# Sheet6.net
KiCad netlist of a schematic drawn in Altium Designer
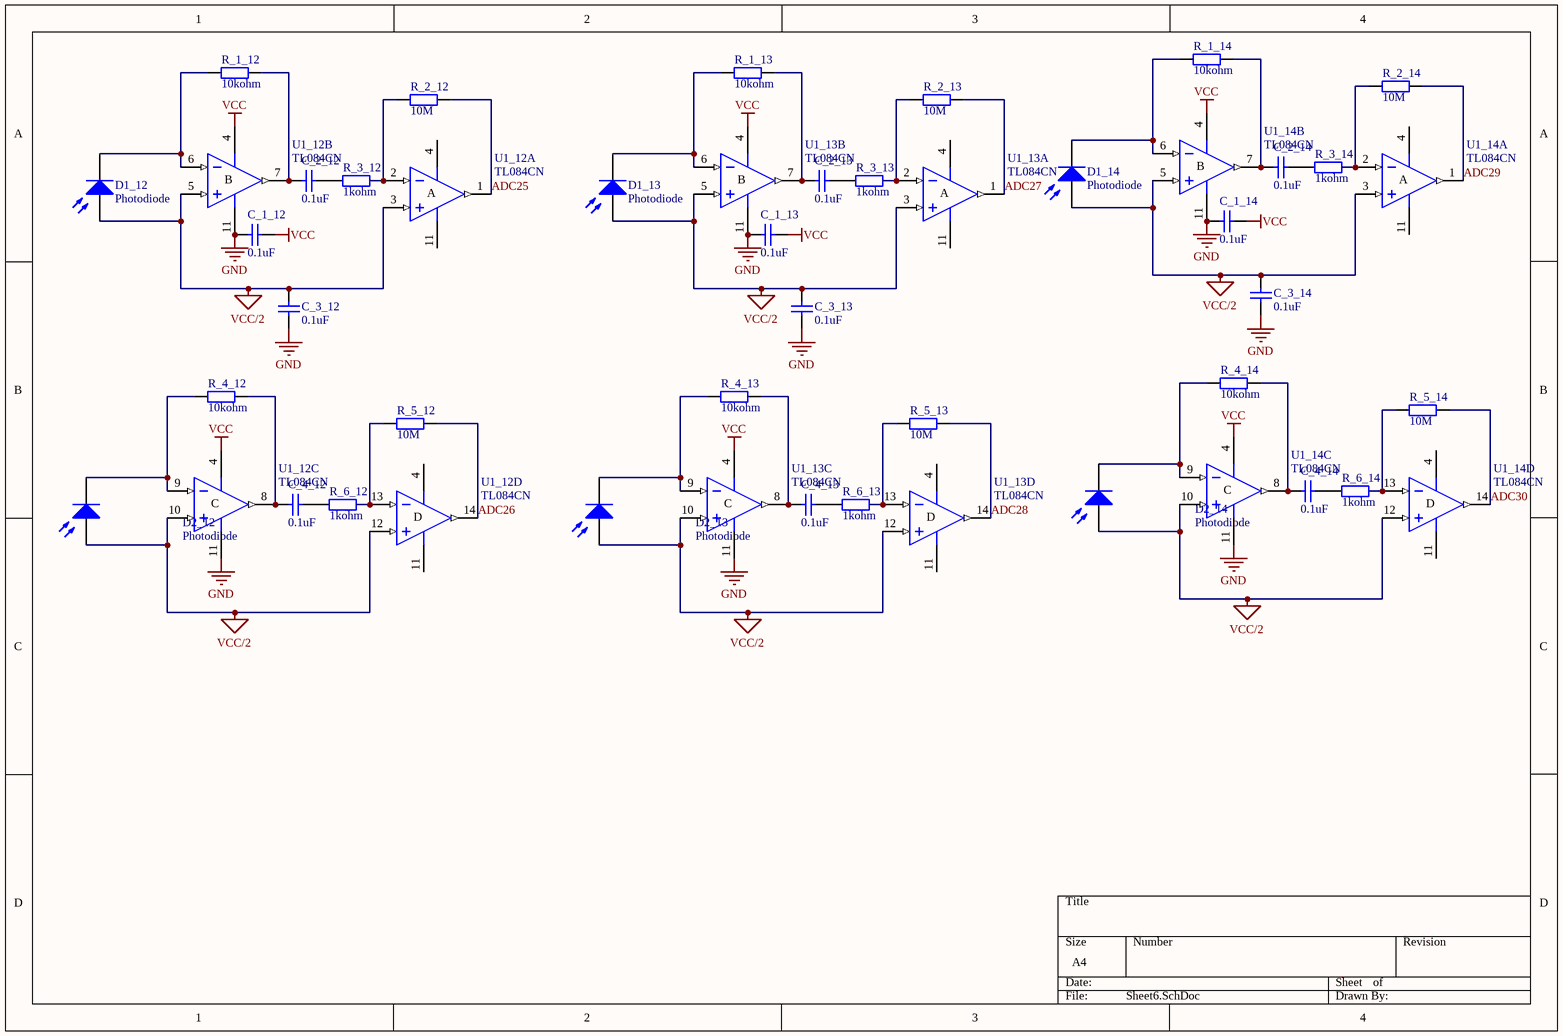
[diagram p0: Sheet6.SchDoc]

(export (version "E")
  (design (tool "Eeschema 10.0.6"))
  (components
    (comp (ref "C_1_12")
      (value "0.1uF")
      (footprint "cms805 - mini")
      (libsource (lib "lib_Robotronik") (part "Capa"))
    )
    (comp (ref "C_1_13")
      (value "0.1uF")
      (footprint "cms805 - mini")
      (libsource (lib "lib_Robotronik") (part "Capa"))
    )
    (comp (ref "C_1_14")
      (value "0.1uF")
      (footprint "cms805 - mini")
      (libsource (lib "lib_Robotronik") (part "Capa"))
    )
    (comp (ref "C_2_12")
      (value "0.1uF")
      (footprint "cms805 - mini")
      (libsource (lib "lib_Robotronik") (part "Capa"))
    )
    (comp (ref "C_2_13")
      (value "0.1uF")
      (footprint "cms805 - mini")
      (libsource (lib "lib_Robotronik") (part "Capa"))
    )
    (comp (ref "C_2_14")
      (value "0.1uF")
      (footprint "cms805 - mini")
      (libsource (lib "lib_Robotronik") (part "Capa"))
    )
    (comp (ref "C_3_12")
      (value "0.1uF")
      (footprint "cms805 - mini")
      (libsource (lib "lib_Robotronik") (part "Capa"))
    )
    (comp (ref "C_3_13")
      (value "0.1uF")
      (footprint "cms805 - mini")
      (libsource (lib "lib_Robotronik") (part "Capa"))
    )
    (comp (ref "C_3_14")
      (value "0.1uF")
      (footprint "cms805 - mini")
      (libsource (lib "lib_Robotronik") (part "Capa"))
    )
    (comp (ref "C_4_12")
      (value "0.1uF")
      (footprint "cms805 - mini")
      (libsource (lib "lib_Robotronik") (part "Capa"))
    )
    (comp (ref "C_4_13")
      (value "0.1uF")
      (footprint "cms805 - mini")
      (libsource (lib "lib_Robotronik") (part "Capa"))
    )
    (comp (ref "C_4_14")
      (value "0.1uF")
      (footprint "cms805 - mini")
      (libsource (lib "lib_Robotronik") (part "Capa"))
    )
    (comp (ref "D1_12")
      (value "Photodiode")
      (footprint "TEMD1000")
      (fields (field (name "PUBLISHER") "Altium Limited"))
      (libsource (lib "lib_Robotronik") (part "Photodiode"))
    )
    (comp (ref "D1_13")
      (value "Photodiode")
      (footprint "TEMD1000")
      (fields (field (name "PUBLISHER") "Altium Limited"))
      (libsource (lib "lib_Robotronik") (part "Photodiode"))
    )
    (comp (ref "D1_14")
      (value "Photodiode")
      (footprint "TEMD1000")
      (fields (field (name "PUBLISHER") "Altium Limited"))
      (libsource (lib "lib_Robotronik") (part "Photodiode"))
    )
    (comp (ref "D2_12")
      (value "Photodiode")
      (footprint "TEMD1000")
      (fields (field (name "PUBLISHER") "Altium Limited"))
      (libsource (lib "lib_Robotronik") (part "Photodiode"))
    )
    (comp (ref "D2_13")
      (value "Photodiode")
      (footprint "TEMD1000")
      (fields (field (name "PUBLISHER") "Altium Limited"))
      (libsource (lib "lib_Robotronik") (part "Photodiode"))
    )
    (comp (ref "D2_14")
      (value "Photodiode")
      (footprint "TEMD1000")
      (fields (field (name "PUBLISHER") "Altium Limited"))
      (libsource (lib "lib_Robotronik") (part "Photodiode"))
    )
    (comp (ref "R_1_12")
      (value "10kohm")
      (footprint "cms805 - mini")
      (libsource (lib "lib_Robotronik") (part "Resistance"))
    )
    (comp (ref "R_1_13")
      (value "10kohm")
      (footprint "cms805 - mini")
      (libsource (lib "lib_Robotronik") (part "Resistance"))
    )
    (comp (ref "R_1_14")
      (value "10kohm")
      (footprint "cms805 - mini")
      (libsource (lib "lib_Robotronik") (part "Resistance"))
    )
    (comp (ref "R_2_12")
      (value "10M")
      (footprint "cms805 - mini")
      (libsource (lib "lib_Robotronik") (part "Resistance"))
    )
    (comp (ref "R_2_13")
      (value "10M")
      (footprint "cms805 - mini")
      (libsource (lib "lib_Robotronik") (part "Resistance"))
    )
    (comp (ref "R_2_14")
      (value "10M")
      (footprint "cms805 - mini")
      (libsource (lib "lib_Robotronik") (part "Resistance"))
    )
    (comp (ref "R_3_12")
      (value "1kohm")
      (footprint "cms805 - mini")
      (libsource (lib "lib_Robotronik") (part "Resistance"))
    )
    (comp (ref "R_3_13")
      (value "1kohm")
      (footprint "cms805 - mini")
      (libsource (lib "lib_Robotronik") (part "Resistance"))
    )
    (comp (ref "R_3_14")
      (value "1kohm")
      (footprint "cms805 - mini")
      (libsource (lib "lib_Robotronik") (part "Resistance"))
    )
    (comp (ref "R_4_12")
      (value "10kohm")
      (footprint "cms805 - mini")
      (libsource (lib "lib_Robotronik") (part "Resistance"))
    )
    (comp (ref "R_4_13")
      (value "10kohm")
      (footprint "cms805 - mini")
      (libsource (lib "lib_Robotronik") (part "Resistance"))
    )
    (comp (ref "R_4_14")
      (value "10kohm")
      (footprint "cms805 - mini")
      (libsource (lib "lib_Robotronik") (part "Resistance"))
    )
    (comp (ref "R_5_12")
      (value "10M")
      (footprint "cms805 - mini")
      (libsource (lib "lib_Robotronik") (part "Resistance"))
    )
    (comp (ref "R_5_13")
      (value "10M")
      (footprint "cms805 - mini")
      (libsource (lib "lib_Robotronik") (part "Resistance"))
    )
    (comp (ref "R_5_14")
      (value "10M")
      (footprint "cms805 - mini")
      (libsource (lib "lib_Robotronik") (part "Resistance"))
    )
    (comp (ref "R_6_12")
      (value "1kohm")
      (footprint "cms805 - mini")
      (libsource (lib "lib_Robotronik") (part "Resistance"))
    )
    (comp (ref "R_6_13")
      (value "1kohm")
      (footprint "cms805 - mini")
      (libsource (lib "lib_Robotronik") (part "Resistance"))
    )
    (comp (ref "R_6_14")
      (value "1kohm")
      (footprint "cms805 - mini")
      (libsource (lib "lib_Robotronik") (part "Resistance"))
    )
    (comp (ref "U1_12")
      (value "TL084CN")
      (footprint "TSSOP14")
      (description "General-Purpose J-FET Quad Operational Amplifier")
      (fields (field (name "PUBLISHER") "Altium Limited"))
      (libsource (lib "lib_Robotronik") (part "TL084CN"))
    )
    (comp (ref "U1_13")
      (value "TL084CN")
      (footprint "TSSOP14")
      (description "General-Purpose J-FET Quad Operational Amplifier")
      (fields (field (name "PUBLISHER") "Altium Limited"))
      (libsource (lib "lib_Robotronik") (part "TL084CN"))
    )
    (comp (ref "U1_14")
      (value "TL084CN")
      (footprint "TSSOP14")
      (description "General-Purpose J-FET Quad Operational Amplifier")
      (fields (field (name "PUBLISHER") "Altium Limited"))
      (libsource (lib "lib_Robotronik") (part "TL084CN"))
    )
  )
  (nets
    (net (code "1") (name "/ADC25") (class "Default")
      (node (ref "R_2_12") (pin "2") (pinfunction "2_2") (pintype "passive"))
      (node (ref "U1_12") (pin "1") (pinfunction "OUT_1") (pintype "output"))
    )
    (net (code "2") (name "/ADC26") (class "Default")
      (node (ref "R_5_12") (pin "2") (pinfunction "2_2") (pintype "passive"))
      (node (ref "U1_12") (pin "14") (pinfunction "OUT_14") (pintype "output"))
    )
    (net (code "3") (name "/ADC27") (class "Default")
      (node (ref "R_2_13") (pin "2") (pinfunction "2_2") (pintype "passive"))
      (node (ref "U1_13") (pin "1") (pinfunction "OUT_1") (pintype "output"))
    )
    (net (code "4") (name "/ADC28") (class "Default")
      (node (ref "R_5_13") (pin "2") (pinfunction "2_2") (pintype "passive"))
      (node (ref "U1_13") (pin "14") (pinfunction "OUT_14") (pintype "output"))
    )
    (net (code "5") (name "/ADC29") (class "Default")
      (node (ref "R_2_14") (pin "2") (pinfunction "2_2") (pintype "passive"))
      (node (ref "U1_14") (pin "1") (pinfunction "OUT_1") (pintype "output"))
    )
    (net (code "6") (name "/ADC30") (class "Default")
      (node (ref "R_5_14") (pin "2") (pinfunction "2_2") (pintype "passive"))
      (node (ref "U1_14") (pin "14") (pinfunction "OUT_14") (pintype "output"))
    )
    (net (code "7") (name "GND") (class "Default")
      (node (ref "C_1_12") (pin "1") (pinfunction "1_1") (pintype "passive"))
      (node (ref "C_1_13") (pin "1") (pinfunction "1_1") (pintype "passive"))
      (node (ref "C_1_14") (pin "1") (pinfunction "1_1") (pintype "passive"))
      (node (ref "C_3_12") (pin "1") (pinfunction "1_1") (pintype "passive"))
      (node (ref "C_3_13") (pin "1") (pinfunction "1_1") (pintype "passive"))
      (node (ref "C_3_14") (pin "1") (pinfunction "1_1") (pintype "passive"))
      (node (ref "U1_12") (pin "11") (pinfunction "V-_11") (pintype "power_in"))
      (node (ref "U1_13") (pin "11") (pinfunction "V-_11") (pintype "power_in"))
      (node (ref "U1_14") (pin "11") (pinfunction "V-_11") (pintype "power_in"))
    )
    (net (code "8") (name "Net-(C_2_12-Pad1)") (class "Default")
      (node (ref "C_2_12") (pin "1") (pinfunction "1_1") (pintype "passive"))
      (node (ref "R_3_12") (pin "1") (pinfunction "1_1") (pintype "passive"))
    )
    (net (code "9") (name "Net-(C_2_13-Pad1)") (class "Default")
      (node (ref "C_2_13") (pin "1") (pinfunction "1_1") (pintype "passive"))
      (node (ref "R_3_13") (pin "1") (pinfunction "1_1") (pintype "passive"))
    )
    (net (code "10") (name "Net-(C_2_14-Pad1)") (class "Default")
      (node (ref "C_2_14") (pin "1") (pinfunction "1_1") (pintype "passive"))
      (node (ref "R_3_14") (pin "1") (pinfunction "1_1") (pintype "passive"))
    )
    (net (code "11") (name "Net-(C_4_12-Pad1)") (class "Default")
      (node (ref "C_4_12") (pin "1") (pinfunction "1_1") (pintype "passive"))
      (node (ref "R_6_12") (pin "1") (pinfunction "1_1") (pintype "passive"))
    )
    (net (code "12") (name "Net-(C_4_13-Pad1)") (class "Default")
      (node (ref "C_4_13") (pin "1") (pinfunction "1_1") (pintype "passive"))
      (node (ref "R_6_13") (pin "1") (pinfunction "1_1") (pintype "passive"))
    )
    (net (code "13") (name "Net-(C_4_14-Pad1)") (class "Default")
      (node (ref "C_4_14") (pin "1") (pinfunction "1_1") (pintype "passive"))
      (node (ref "R_6_14") (pin "1") (pinfunction "1_1") (pintype "passive"))
    )
    (net (code "14") (name "Net-(D1_12-K)") (class "Default")
      (node (ref "D1_12") (pin "2") (pinfunction "K_2") (pintype "passive"))
      (node (ref "R_1_12") (pin "1") (pinfunction "1_1") (pintype "passive"))
      (node (ref "U1_12") (pin "6") (pinfunction "IN-_6") (pintype "input"))
    )
    (net (code "15") (name "Net-(D1_13-K)") (class "Default")
      (node (ref "D1_13") (pin "2") (pinfunction "K_2") (pintype "passive"))
      (node (ref "R_1_13") (pin "1") (pinfunction "1_1") (pintype "passive"))
      (node (ref "U1_13") (pin "6") (pinfunction "IN-_6") (pintype "input"))
    )
    (net (code "16") (name "Net-(D1_14-K)") (class "Default")
      (node (ref "D1_14") (pin "2") (pinfunction "K_2") (pintype "passive"))
      (node (ref "R_1_14") (pin "1") (pinfunction "1_1") (pintype "passive"))
      (node (ref "U1_14") (pin "6") (pinfunction "IN-_6") (pintype "input"))
    )
    (net (code "17") (name "Net-(D2_12-K)") (class "Default")
      (node (ref "D2_12") (pin "2") (pinfunction "K_2") (pintype "passive"))
      (node (ref "R_4_12") (pin "1") (pinfunction "1_1") (pintype "passive"))
      (node (ref "U1_12") (pin "9") (pinfunction "IN-_9") (pintype "input"))
    )
    (net (code "18") (name "Net-(D2_13-K)") (class "Default")
      (node (ref "D2_13") (pin "2") (pinfunction "K_2") (pintype "passive"))
      (node (ref "R_4_13") (pin "1") (pinfunction "1_1") (pintype "passive"))
      (node (ref "U1_13") (pin "9") (pinfunction "IN-_9") (pintype "input"))
    )
    (net (code "19") (name "Net-(D2_14-K)") (class "Default")
      (node (ref "D2_14") (pin "2") (pinfunction "K_2") (pintype "passive"))
      (node (ref "R_4_14") (pin "1") (pinfunction "1_1") (pintype "passive"))
      (node (ref "U1_14") (pin "9") (pinfunction "IN-_9") (pintype "input"))
    )
    (net (code "20") (name "Net-(U1_12A-IN-)") (class "Default")
      (node (ref "R_2_12") (pin "1") (pinfunction "1_1") (pintype "passive"))
      (node (ref "R_3_12") (pin "2") (pinfunction "2_2") (pintype "passive"))
      (node (ref "U1_12") (pin "2") (pinfunction "IN-_2") (pintype "input"))
    )
    (net (code "21") (name "Net-(U1_12B-OUT)") (class "Default")
      (node (ref "C_2_12") (pin "2") (pinfunction "2_2") (pintype "passive"))
      (node (ref "R_1_12") (pin "2") (pinfunction "2_2") (pintype "passive"))
      (node (ref "U1_12") (pin "7") (pinfunction "OUT_7") (pintype "output"))
    )
    (net (code "22") (name "Net-(U1_12C-OUT)") (class "Default")
      (node (ref "C_4_12") (pin "2") (pinfunction "2_2") (pintype "passive"))
      (node (ref "R_4_12") (pin "2") (pinfunction "2_2") (pintype "passive"))
      (node (ref "U1_12") (pin "8") (pinfunction "OUT_8") (pintype "output"))
    )
    (net (code "23") (name "Net-(U1_12D-IN-)") (class "Default")
      (node (ref "R_5_12") (pin "1") (pinfunction "1_1") (pintype "passive"))
      (node (ref "R_6_12") (pin "2") (pinfunction "2_2") (pintype "passive"))
      (node (ref "U1_12") (pin "13") (pinfunction "IN-_13") (pintype "input"))
    )
    (net (code "24") (name "Net-(U1_13A-IN-)") (class "Default")
      (node (ref "R_2_13") (pin "1") (pinfunction "1_1") (pintype "passive"))
      (node (ref "R_3_13") (pin "2") (pinfunction "2_2") (pintype "passive"))
      (node (ref "U1_13") (pin "2") (pinfunction "IN-_2") (pintype "input"))
    )
    (net (code "25") (name "Net-(U1_13B-OUT)") (class "Default")
      (node (ref "C_2_13") (pin "2") (pinfunction "2_2") (pintype "passive"))
      (node (ref "R_1_13") (pin "2") (pinfunction "2_2") (pintype "passive"))
      (node (ref "U1_13") (pin "7") (pinfunction "OUT_7") (pintype "output"))
    )
    (net (code "26") (name "Net-(U1_13C-OUT)") (class "Default")
      (node (ref "C_4_13") (pin "2") (pinfunction "2_2") (pintype "passive"))
      (node (ref "R_4_13") (pin "2") (pinfunction "2_2") (pintype "passive"))
      (node (ref "U1_13") (pin "8") (pinfunction "OUT_8") (pintype "output"))
    )
    (net (code "27") (name "Net-(U1_13D-IN-)") (class "Default")
      (node (ref "R_5_13") (pin "1") (pinfunction "1_1") (pintype "passive"))
      (node (ref "R_6_13") (pin "2") (pinfunction "2_2") (pintype "passive"))
      (node (ref "U1_13") (pin "13") (pinfunction "IN-_13") (pintype "input"))
    )
    (net (code "28") (name "Net-(U1_14A-IN-)") (class "Default")
      (node (ref "R_2_14") (pin "1") (pinfunction "1_1") (pintype "passive"))
      (node (ref "R_3_14") (pin "2") (pinfunction "2_2") (pintype "passive"))
      (node (ref "U1_14") (pin "2") (pinfunction "IN-_2") (pintype "input"))
    )
    (net (code "29") (name "Net-(U1_14B-OUT)") (class "Default")
      (node (ref "C_2_14") (pin "2") (pinfunction "2_2") (pintype "passive"))
      (node (ref "R_1_14") (pin "2") (pinfunction "2_2") (pintype "passive"))
      (node (ref "U1_14") (pin "7") (pinfunction "OUT_7") (pintype "output"))
    )
    (net (code "30") (name "Net-(U1_14C-OUT)") (class "Default")
      (node (ref "C_4_14") (pin "2") (pinfunction "2_2") (pintype "passive"))
      (node (ref "R_4_14") (pin "2") (pinfunction "2_2") (pintype "passive"))
      (node (ref "U1_14") (pin "8") (pinfunction "OUT_8") (pintype "output"))
    )
    (net (code "31") (name "Net-(U1_14D-IN-)") (class "Default")
      (node (ref "R_5_14") (pin "1") (pinfunction "1_1") (pintype "passive"))
      (node (ref "R_6_14") (pin "2") (pinfunction "2_2") (pintype "passive"))
      (node (ref "U1_14") (pin "13") (pinfunction "IN-_13") (pintype "input"))
    )
    (net (code "32") (name "VCC") (class "Default")
      (node (ref "C_1_12") (pin "2") (pinfunction "2_2") (pintype "passive"))
      (node (ref "C_1_13") (pin "2") (pinfunction "2_2") (pintype "passive"))
      (node (ref "C_1_14") (pin "2") (pinfunction "2_2") (pintype "passive"))
      (node (ref "U1_12") (pin "4") (pinfunction "V+_4") (pintype "power_in"))
      (node (ref "U1_13") (pin "4") (pinfunction "V+_4") (pintype "power_in"))
      (node (ref "U1_14") (pin "4") (pinfunction "V+_4") (pintype "power_in"))
    )
    (net (code "33") (name "VCC{slash}2") (class "Default")
      (node (ref "C_3_12") (pin "2") (pinfunction "2_2") (pintype "passive"))
      (node (ref "C_3_13") (pin "2") (pinfunction "2_2") (pintype "passive"))
      (node (ref "C_3_14") (pin "2") (pinfunction "2_2") (pintype "passive"))
      (node (ref "D1_12") (pin "1") (pinfunction "A_1") (pintype "passive"))
      (node (ref "D1_13") (pin "1") (pinfunction "A_1") (pintype "passive"))
      (node (ref "D1_14") (pin "1") (pinfunction "A_1") (pintype "passive"))
      (node (ref "D2_12") (pin "1") (pinfunction "A_1") (pintype "passive"))
      (node (ref "D2_13") (pin "1") (pinfunction "A_1") (pintype "passive"))
      (node (ref "D2_14") (pin "1") (pinfunction "A_1") (pintype "passive"))
      (node (ref "U1_12") (pin "10") (pinfunction "IN+_10") (pintype "input"))
      (node (ref "U1_12") (pin "12") (pinfunction "IN+_12") (pintype "input"))
      (node (ref "U1_12") (pin "3") (pinfunction "IN+_3") (pintype "input"))
      (node (ref "U1_12") (pin "5") (pinfunction "IN+_5") (pintype "input"))
      (node (ref "U1_13") (pin "10") (pinfunction "IN+_10") (pintype "input"))
      (node (ref "U1_13") (pin "12") (pinfunction "IN+_12") (pintype "input"))
      (node (ref "U1_13") (pin "3") (pinfunction "IN+_3") (pintype "input"))
      (node (ref "U1_13") (pin "5") (pinfunction "IN+_5") (pintype "input"))
      (node (ref "U1_14") (pin "10") (pinfunction "IN+_10") (pintype "input"))
      (node (ref "U1_14") (pin "12") (pinfunction "IN+_12") (pintype "input"))
      (node (ref "U1_14") (pin "3") (pinfunction "IN+_3") (pintype "input"))
      (node (ref "U1_14") (pin "5") (pinfunction "IN+_5") (pintype "input"))
    )
    (net (code "34") (name "unconnected-(U1_12A-V+-Pad4)") (class "Default")
      (node (ref "U1_12") (pin "4") (pinfunction "V+_4") (pintype "power_in"))
    )
    (net (code "35") (name "unconnected-(U1_12A-V--Pad11)") (class "Default")
      (node (ref "U1_12") (pin "11") (pinfunction "V-_11") (pintype "power_in"))
    )
    (net (code "36") (name "unconnected-(U1_12D-V+-Pad4)") (class "Default")
      (node (ref "U1_12") (pin "4") (pinfunction "V+_4") (pintype "power_in"))
    )
    (net (code "37") (name "unconnected-(U1_12D-V--Pad11)") (class "Default")
      (node (ref "U1_12") (pin "11") (pinfunction "V-_11") (pintype "power_in"))
    )
    (net (code "38") (name "unconnected-(U1_13A-V+-Pad4)") (class "Default")
      (node (ref "U1_13") (pin "4") (pinfunction "V+_4") (pintype "power_in"))
    )
    (net (code "39") (name "unconnected-(U1_13A-V--Pad11)") (class "Default")
      (node (ref "U1_13") (pin "11") (pinfunction "V-_11") (pintype "power_in"))
    )
    (net (code "40") (name "unconnected-(U1_13D-V+-Pad4)") (class "Default")
      (node (ref "U1_13") (pin "4") (pinfunction "V+_4") (pintype "power_in"))
    )
    (net (code "41") (name "unconnected-(U1_13D-V--Pad11)") (class "Default")
      (node (ref "U1_13") (pin "11") (pinfunction "V-_11") (pintype "power_in"))
    )
    (net (code "42") (name "unconnected-(U1_14A-V+-Pad4)") (class "Default")
      (node (ref "U1_14") (pin "4") (pinfunction "V+_4") (pintype "power_in"))
    )
    (net (code "43") (name "unconnected-(U1_14A-V--Pad11)") (class "Default")
      (node (ref "U1_14") (pin "11") (pinfunction "V-_11") (pintype "power_in"))
    )
    (net (code "44") (name "unconnected-(U1_14D-V+-Pad4)") (class "Default")
      (node (ref "U1_14") (pin "4") (pinfunction "V+_4") (pintype "power_in"))
    )
    (net (code "45") (name "unconnected-(U1_14D-V--Pad11)") (class "Default")
      (node (ref "U1_14") (pin "11") (pinfunction "V-_11") (pintype "power_in"))
    )
  )
)
